# Sheet.net
KiCad netlist of a schematic drawn in Altium Designer
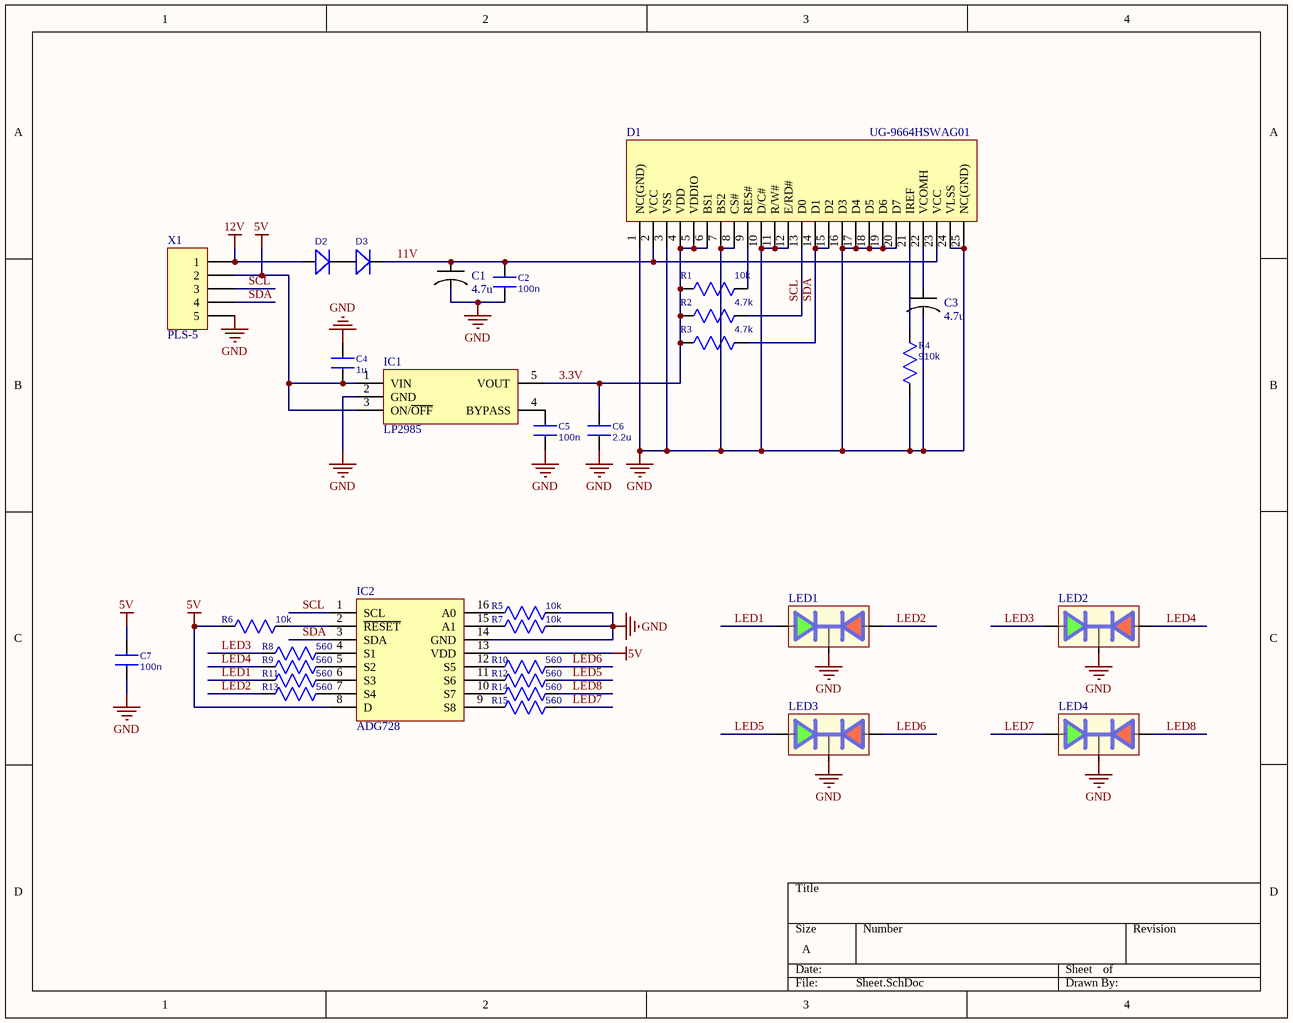
[diagram p0: Sheet.SchDoc]

(export (version "E")
  (design (tool "Eeschema 10.0.6"))
  (components
    (comp (ref "C1")
      (value "4.7u")
      (footprint "R79")
      (description "Electrolit capasitor")
      (libsource (lib "SmartOutletIntegratedLibrary") (part "Electrolit"))
    )
    (comp (ref "C2")
      (value "100n")
      (footprint "C_0603")
      (description "Capacitor")
      (libsource (lib "AX_Altium_v2.3") (part "C0603"))
    )
    (comp (ref "C3")
      (value "4.7u")
      (footprint "R79")
      (description "Electrolit capasitor")
      (libsource (lib "SmartOutletIntegratedLibrary") (part "Electrolit"))
    )
    (comp (ref "C4")
      (value "1u")
      (footprint "C_0603")
      (description "Capacitor")
      (libsource (lib "AX_Altium_v2.3") (part "C0603"))
    )
    (comp (ref "C5")
      (value "100n")
      (footprint "C_0603")
      (description "Capacitor")
      (libsource (lib "AX_Altium_v2.3") (part "C0603"))
    )
    (comp (ref "C6")
      (value "2.2u")
      (footprint "C_0603")
      (description "Capacitor")
      (libsource (lib "AX_Altium_v2.3") (part "C0603"))
    )
    (comp (ref "C7")
      (value "100n")
      (footprint "C_0603")
      (description "Capacitor")
      (libsource (lib "AX_Altium_v2.3") (part "C0603"))
    )
    (comp (ref "D1")
      (value "UG-9664HSWAG01")
      (footprint "UG-9664HSWAG01")
      (description "Display")
      (libsource (lib "SmartOutletIntegratedLibrary") (part "UG-9664HSWAG01"))
    )
    (comp (ref "D2")
      (value "D_DO-214AC")
      (footprint "DO-214AC")
      (description "Diode")
      (libsource (lib "AX_Altium_v2.3") (part "D_DO-214AC"))
    )
    (comp (ref "D3")
      (value "D_DO-214AC")
      (footprint "DO-214AC")
      (description "Diode")
      (libsource (lib "AX_Altium_v2.3") (part "D_DO-214AC"))
    )
    (comp (ref "IC1")
      (value "LP2985")
      (footprint "SOT23-5")
      (description "150-mA Low-noise Low-dropout Regulator With Shutdown")
      (libsource (lib "SmartOutletIntegratedLibrary") (part "LP2985"))
    )
    (comp (ref "IC2")
      (value "ADG728")
      (footprint "SSOP-16")
      (description "2-Wire Serially Controlled, Matrix Switches")
      (libsource (lib "SmartOutletIntegratedLibrary") (part "ADG728"))
    )
    (comp (ref "LED1")
      (value "GNL-3015")
      (footprint "GNL-3015")
      (description "Bi-color LED")
      (libsource (lib "SmartOutletIntegratedLibrary") (part "GNL-3015"))
    )
    (comp (ref "LED2")
      (value "GNL-3015")
      (footprint "GNL-3015")
      (description "Bi-color LED")
      (libsource (lib "SmartOutletIntegratedLibrary") (part "GNL-3015"))
    )
    (comp (ref "LED3")
      (value "GNL-3015")
      (footprint "GNL-3015")
      (description "Bi-color LED")
      (libsource (lib "SmartOutletIntegratedLibrary") (part "GNL-3015"))
    )
    (comp (ref "LED4")
      (value "GNL-3015")
      (footprint "GNL-3015")
      (description "Bi-color LED")
      (libsource (lib "SmartOutletIntegratedLibrary") (part "GNL-3015"))
    )
    (comp (ref "R1")
      (value "10k")
      (footprint "R_0603")
      (description "Resistor")
      (libsource (lib "AX_Altium_v2.3") (part "R0603"))
    )
    (comp (ref "R2")
      (value "4.7k")
      (footprint "R_0603")
      (description "Resistor")
      (libsource (lib "AX_Altium_v2.3") (part "R0603"))
    )
    (comp (ref "R3")
      (value "4.7k")
      (footprint "R_0603")
      (description "Resistor")
      (libsource (lib "AX_Altium_v2.3") (part "R0603"))
    )
    (comp (ref "R4")
      (value "910k")
      (footprint "R_0603")
      (description "Resistor")
      (libsource (lib "AX_Altium_v2.3") (part "R0603"))
    )
    (comp (ref "R5")
      (value "10k")
      (footprint "R_0603")
      (description "Resistor")
      (libsource (lib "AX_Altium_v2.3") (part "R0603"))
    )
    (comp (ref "R6")
      (value "10k")
      (footprint "R_0603")
      (description "Resistor")
      (libsource (lib "AX_Altium_v2.3") (part "R0603"))
    )
    (comp (ref "R7")
      (value "10k")
      (footprint "R_0603")
      (description "Resistor")
      (libsource (lib "AX_Altium_v2.3") (part "R0603"))
    )
    (comp (ref "R8")
      (value "560")
      (footprint "R_0603")
      (description "Resistor")
      (libsource (lib "AX_Altium_v2.3") (part "R0603"))
    )
    (comp (ref "R9")
      (value "560")
      (footprint "R_0603")
      (description "Resistor")
      (libsource (lib "AX_Altium_v2.3") (part "R0603"))
    )
    (comp (ref "R10")
      (value "560")
      (footprint "R_0603")
      (description "Resistor")
      (libsource (lib "AX_Altium_v2.3") (part "R0603"))
    )
    (comp (ref "R11")
      (value "560")
      (footprint "R_0603")
      (description "Resistor")
      (libsource (lib "AX_Altium_v2.3") (part "R0603"))
    )
    (comp (ref "R12")
      (value "560")
      (footprint "R_0603")
      (description "Resistor")
      (libsource (lib "AX_Altium_v2.3") (part "R0603"))
    )
    (comp (ref "R13")
      (value "560")
      (footprint "R_0603")
      (description "Resistor")
      (libsource (lib "AX_Altium_v2.3") (part "R0603"))
    )
    (comp (ref "R14")
      (value "560")
      (footprint "R_0603")
      (description "Resistor")
      (libsource (lib "AX_Altium_v2.3") (part "R0603"))
    )
    (comp (ref "R15")
      (value "560")
      (footprint "R_0603")
      (description "Resistor")
      (libsource (lib "AX_Altium_v2.3") (part "R0603"))
    )
    (comp (ref "X1")
      (value "PLS-5")
      (footprint "PLS-5-3D")
      (description "Header, 5-Pin")
      (fields (field (name "PUBLISHER") "Altium Limited"))
      (libsource (lib "AX_Altium_v2.3") (part "PLS-5"))
    )
  )
  (nets
    (net (code "1") (name "/3.3V") (class "Default")
      (node (ref "C6") (pin "1") (pintype "passive"))
      (node (ref "D1") (pin "4") (pinfunction "VDD_4") (pintype "passive"))
      (node (ref "D1") (pin "5") (pinfunction "VDDIO_5") (pintype "passive"))
      (node (ref "D1") (pin "6") (pinfunction "BS1_6") (pintype "passive"))
      (node (ref "IC1") (pin "5") (pinfunction "VOUT_5") (pintype "passive"))
      (node (ref "R1") (pin "1") (pintype "passive"))
      (node (ref "R2") (pin "1") (pintype "passive"))
      (node (ref "R3") (pin "1") (pintype "passive"))
    )
    (net (code "2") (name "/11V") (class "Default")
      (node (ref "C1") (pin "1") (pinfunction "1_1") (pintype "passive"))
      (node (ref "C2") (pin "2") (pintype "passive"))
      (node (ref "D1") (pin "2") (pinfunction "VCC_2") (pintype "passive"))
      (node (ref "D1") (pin "23") (pinfunction "VCC_23") (pintype "passive"))
      (node (ref "D3") (pin "2") (pinfunction "K_2") (pintype "passive"))
    )
    (net (code "3") (name "/LED1") (class "Default")
      (node (ref "LED1") (pin "1") (pinfunction "1_1") (pintype "passive"))
      (node (ref "R11") (pin "1") (pintype "passive"))
    )
    (net (code "4") (name "/LED2") (class "Default")
      (node (ref "LED1") (pin "3") (pinfunction "3_3") (pintype "passive"))
      (node (ref "R13") (pin "1") (pintype "passive"))
    )
    (net (code "5") (name "/LED3") (class "Default")
      (node (ref "LED2") (pin "1") (pinfunction "1_1") (pintype "passive"))
      (node (ref "R8") (pin "1") (pintype "passive"))
    )
    (net (code "6") (name "/LED4") (class "Default")
      (node (ref "LED2") (pin "3") (pinfunction "3_3") (pintype "passive"))
      (node (ref "R9") (pin "1") (pintype "passive"))
    )
    (net (code "7") (name "/LED5") (class "Default")
      (node (ref "LED3") (pin "1") (pinfunction "1_1") (pintype "passive"))
      (node (ref "R12") (pin "2") (pintype "passive"))
    )
    (net (code "8") (name "/LED6") (class "Default")
      (node (ref "LED3") (pin "3") (pinfunction "3_3") (pintype "passive"))
      (node (ref "R10") (pin "2") (pintype "passive"))
    )
    (net (code "9") (name "/LED7") (class "Default")
      (node (ref "LED4") (pin "1") (pinfunction "1_1") (pintype "passive"))
      (node (ref "R15") (pin "2") (pintype "passive"))
    )
    (net (code "10") (name "/LED8") (class "Default")
      (node (ref "LED4") (pin "3") (pinfunction "3_3") (pintype "passive"))
      (node (ref "R14") (pin "2") (pintype "passive"))
    )
    (net (code "11") (name "/SCL") (class "Default")
      (node (ref "D1") (pin "13") (pinfunction "D0_13") (pintype "passive"))
      (node (ref "IC2") (pin "1") (pinfunction "SCL_1") (pintype "passive"))
      (node (ref "R2") (pin "2") (pintype "passive"))
      (node (ref "X1") (pin "3") (pinfunction "3_3") (pintype "passive"))
    )
    (net (code "12") (name "/SDA") (class "Default")
      (node (ref "D1") (pin "14") (pinfunction "D1_14") (pintype "passive"))
      (node (ref "D1") (pin "15") (pinfunction "D2_15") (pintype "passive"))
      (node (ref "IC2") (pin "3") (pinfunction "SDA_3") (pintype "passive"))
      (node (ref "R3") (pin "2") (pintype "passive"))
      (node (ref "X1") (pin "4") (pinfunction "4_4") (pintype "passive"))
    )
    (net (code "13") (name "5V") (class "Default")
      (node (ref "C4") (pin "1") (pintype "passive"))
      (node (ref "C7") (pin "1") (pintype "passive"))
      (node (ref "IC1") (pin "1") (pinfunction "VIN_1") (pintype "passive"))
      (node (ref "IC1") (pin "3") (pinfunction "ON/~{OFF}_3") (pintype "passive"))
      (node (ref "IC2") (pin "13") (pinfunction "VDD_13") (pintype "passive"))
      (node (ref "IC2") (pin "8") (pinfunction "D_8") (pintype "passive"))
      (node (ref "R6") (pin "1") (pintype "passive"))
      (node (ref "X1") (pin "2") (pinfunction "2_2") (pintype "passive"))
    )
    (net (code "14") (name "12V") (class "Default")
      (node (ref "D2") (pin "1") (pinfunction "A_1") (pintype "passive"))
      (node (ref "X1") (pin "1") (pinfunction "1_1") (pintype "passive"))
    )
    (net (code "15") (name "GND") (class "Default")
      (node (ref "C1") (pin "2") (pinfunction "2_2") (pintype "passive"))
      (node (ref "C2") (pin "1") (pintype "passive"))
      (node (ref "C3") (pin "2") (pinfunction "2_2") (pintype "passive"))
      (node (ref "C4") (pin "2") (pintype "passive"))
      (node (ref "C5") (pin "2") (pintype "passive"))
      (node (ref "C6") (pin "2") (pintype "passive"))
      (node (ref "C7") (pin "2") (pintype "passive"))
      (node (ref "D1") (pin "1") (pinfunction "NC(GND)_1") (pintype "passive"))
      (node (ref "D1") (pin "10") (pinfunction "D/C#_10") (pintype "passive"))
      (node (ref "D1") (pin "11") (pinfunction "R/W#_11") (pintype "passive"))
      (node (ref "D1") (pin "12") (pinfunction "E/RD#_12") (pintype "passive"))
      (node (ref "D1") (pin "16") (pinfunction "D3_16") (pintype "passive"))
      (node (ref "D1") (pin "17") (pinfunction "D4_17") (pintype "passive"))
      (node (ref "D1") (pin "18") (pinfunction "D5_18") (pintype "passive"))
      (node (ref "D1") (pin "19") (pinfunction "D6_19") (pintype "passive"))
      (node (ref "D1") (pin "20") (pinfunction "D7_20") (pintype "passive"))
      (node (ref "D1") (pin "24") (pinfunction "VLSS_24") (pintype "passive"))
      (node (ref "D1") (pin "25") (pinfunction "NC(GND)_25") (pintype "passive"))
      (node (ref "D1") (pin "3") (pinfunction "VSS_3") (pintype "passive"))
      (node (ref "D1") (pin "7") (pinfunction "BS2_7") (pintype "passive"))
      (node (ref "D1") (pin "8") (pinfunction "CS#_8") (pintype "passive"))
      (node (ref "IC1") (pin "2") (pinfunction "GND_2") (pintype "passive"))
      (node (ref "IC2") (pin "14") (pinfunction "GND_14") (pintype "passive"))
      (node (ref "LED1") (pin "2") (pinfunction "2_2") (pintype "passive"))
      (node (ref "LED2") (pin "2") (pinfunction "2_2") (pintype "passive"))
      (node (ref "LED3") (pin "2") (pinfunction "2_2") (pintype "passive"))
      (node (ref "LED4") (pin "2") (pinfunction "2_2") (pintype "passive"))
      (node (ref "R4") (pin "2") (pintype "passive"))
      (node (ref "R5") (pin "2") (pintype "passive"))
      (node (ref "R7") (pin "2") (pintype "passive"))
      (node (ref "X1") (pin "5") (pinfunction "5_5") (pintype "passive"))
    )
    (net (code "16") (name "Net-(D1-IREF)") (class "Default")
      (node (ref "D1") (pin "21") (pinfunction "IREF_21") (pintype "passive"))
      (node (ref "R4") (pin "1") (pintype "passive"))
    )
    (net (code "17") (name "Net-(D1-RES#)") (class "Default")
      (node (ref "D1") (pin "9") (pinfunction "RES#_9") (pintype "passive"))
      (node (ref "R1") (pin "2") (pintype "passive"))
    )
    (net (code "18") (name "Net-(D1-VCOMH)") (class "Default")
      (node (ref "C3") (pin "1") (pinfunction "1_1") (pintype "passive"))
      (node (ref "D1") (pin "22") (pinfunction "VCOMH_22") (pintype "passive"))
    )
    (net (code "19") (name "Net-(D2-K)") (class "Default")
      (node (ref "D2") (pin "2") (pinfunction "K_2") (pintype "passive"))
      (node (ref "D3") (pin "1") (pinfunction "A_1") (pintype "passive"))
    )
    (net (code "20") (name "Net-(IC1-BYPASS)") (class "Default")
      (node (ref "C5") (pin "1") (pintype "passive"))
      (node (ref "IC1") (pin "4") (pinfunction "BYPASS_4") (pintype "passive"))
    )
    (net (code "21") (name "Net-(IC2-A0)") (class "Default")
      (node (ref "IC2") (pin "16") (pinfunction "A0_16") (pintype "passive"))
      (node (ref "R5") (pin "1") (pintype "passive"))
    )
    (net (code "22") (name "Net-(IC2-A1)") (class "Default")
      (node (ref "IC2") (pin "15") (pinfunction "A1_15") (pintype "passive"))
      (node (ref "R7") (pin "1") (pintype "passive"))
    )
    (net (code "23") (name "Net-(IC2-S1)") (class "Default")
      (node (ref "IC2") (pin "4") (pinfunction "S1_4") (pintype "passive"))
      (node (ref "R8") (pin "2") (pintype "passive"))
    )
    (net (code "24") (name "Net-(IC2-S2)") (class "Default")
      (node (ref "IC2") (pin "5") (pinfunction "S2_5") (pintype "passive"))
      (node (ref "R9") (pin "2") (pintype "passive"))
    )
    (net (code "25") (name "Net-(IC2-S3)") (class "Default")
      (node (ref "IC2") (pin "6") (pinfunction "S3_6") (pintype "passive"))
      (node (ref "R11") (pin "2") (pintype "passive"))
    )
    (net (code "26") (name "Net-(IC2-S4)") (class "Default")
      (node (ref "IC2") (pin "7") (pinfunction "S4_7") (pintype "passive"))
      (node (ref "R13") (pin "2") (pintype "passive"))
    )
    (net (code "27") (name "Net-(IC2-S5)") (class "Default")
      (node (ref "IC2") (pin "12") (pinfunction "S5_12") (pintype "passive"))
      (node (ref "R10") (pin "1") (pintype "passive"))
    )
    (net (code "28") (name "Net-(IC2-S6)") (class "Default")
      (node (ref "IC2") (pin "11") (pinfunction "S6_11") (pintype "passive"))
      (node (ref "R12") (pin "1") (pintype "passive"))
    )
    (net (code "29") (name "Net-(IC2-S7)") (class "Default")
      (node (ref "IC2") (pin "10") (pinfunction "S7_10") (pintype "passive"))
      (node (ref "R14") (pin "1") (pintype "passive"))
    )
    (net (code "30") (name "Net-(IC2-S8)") (class "Default")
      (node (ref "IC2") (pin "9") (pinfunction "S8_9") (pintype "passive"))
      (node (ref "R15") (pin "1") (pintype "passive"))
    )
    (net (code "31") (name "Net-(IC2-~{RESET})") (class "Default")
      (node (ref "IC2") (pin "2") (pinfunction "~{RESET}_2") (pintype "passive"))
      (node (ref "R6") (pin "2") (pintype "passive"))
    )
  )
)
